# projeson.net
KiCad netlist of a schematic drawn in EAGLE
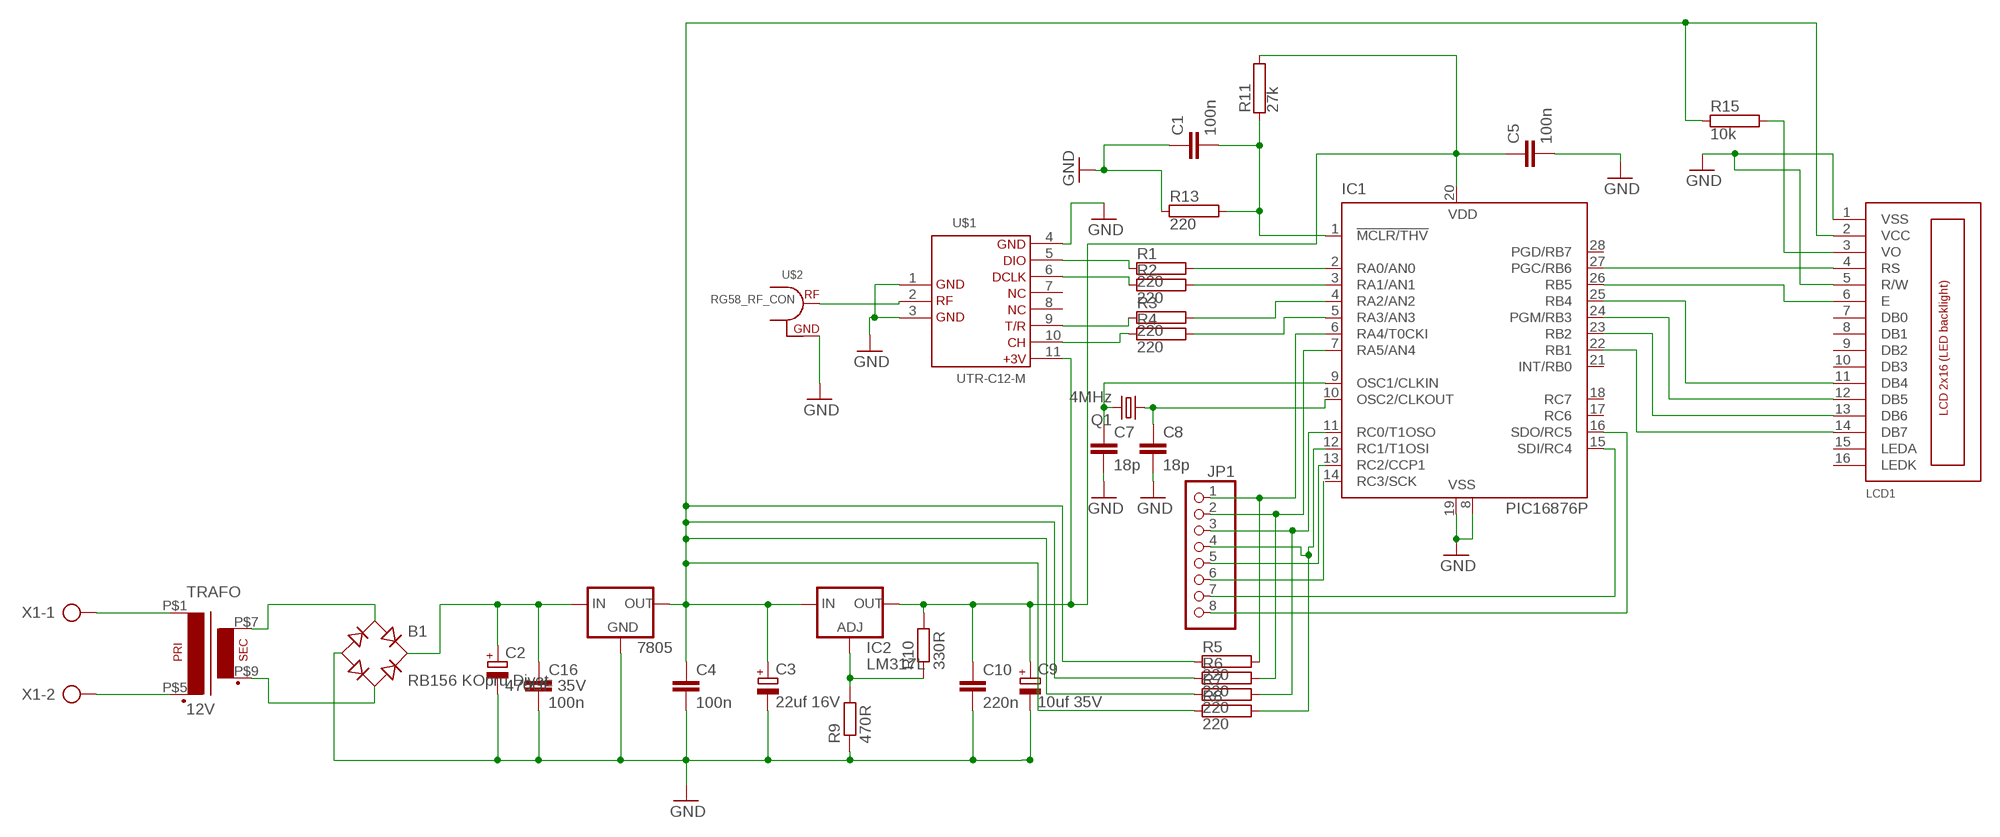
[diagram p0: schematic, sheet 1]

(export (version "E")
  (design (tool "Eeschema 10.0.6"))
  (components
    (comp (ref "7805")
      (value "78XXS")
      (footprint "eagle-import:78XXS")
      (libsource (lib "eagle-import") (part "78XXS"))
    )
    (comp (ref "B1")
      (value "RB156 KOpru Diyot")
      (footprint "eagle-import:RB1A")
      (libsource (lib "eagle-import") (part "RB1A"))
    )
    (comp (ref "C1")
      (value "100n")
      (footprint "eagle-import:C025-030X050")
      (libsource (lib "eagle-import") (part "C-EU025-030X050"))
    )
    (comp (ref "C2")
      (value "470UF 35V")
      (footprint "eagle-import:E3,5-10")
      (libsource (lib "eagle-import") (part "CPOL-EUE3.5-10"))
    )
    (comp (ref "C3")
      (value "22uf 16V")
      (footprint "eagle-import:E2,5-7")
      (libsource (lib "eagle-import") (part "CPOL-EUE2.5-7"))
    )
    (comp (ref "C4")
      (value "100n")
      (footprint "eagle-import:C050-025X075")
      (libsource (lib "eagle-import") (part "C-EU050-025X075"))
    )
    (comp (ref "C5")
      (value "100n")
      (footprint "eagle-import:C025-025X050")
      (libsource (lib "eagle-import") (part "C-EU025-025X050"))
    )
    (comp (ref "C7")
      (value "18p")
      (footprint "eagle-import:C025-025X050")
      (libsource (lib "eagle-import") (part "C-EU025-025X050"))
    )
    (comp (ref "C8")
      (value "18p")
      (footprint "eagle-import:C025-025X050")
      (libsource (lib "eagle-import") (part "C-EU025-025X050"))
    )
    (comp (ref "C9")
      (value "10uf 35V")
      (footprint "eagle-import:E2,5-7")
      (libsource (lib "eagle-import") (part "CPOL-EUE2.5-7"))
    )
    (comp (ref "C10")
      (value "220n")
      (footprint "eagle-import:C050-025X075")
      (libsource (lib "eagle-import") (part "C-EU050-025X075"))
    )
    (comp (ref "C16")
      (value "100n")
      (footprint "eagle-import:C050-025X075")
      (libsource (lib "eagle-import") (part "C-EU050-025X075"))
    )
    (comp (ref "IC1")
      (value "PIC16876P")
      (footprint "eagle-import:DIL28-3")
      (libsource (lib "eagle-import") (part "PIC16876P"))
    )
    (comp (ref "IC2")
      (value "LM317L")
      (footprint "eagle-import:317L")
      (libsource (lib "eagle-import") (part "LM317L"))
    )
    (comp (ref "JP1")
      (value "PINHD-1X8")
      (footprint "eagle-import:1X08")
      (libsource (lib "eagle-import") (part "PINHD-1X8"))
    )
    (comp (ref "LCD1")
      (value "LCD_2X16_SIL")
      (footprint "eagle-import:HY-1602F")
      (libsource (lib "eagle-import") (part "LCD_2X16_SIL"))
    )
    (comp (ref "Q1")
      (value "4MHz")
      (footprint "eagle-import:HC49_S")
      (libsource (lib "eagle-import") (part "CRYTALHC49S"))
    )
    (comp (ref "R1")
      (value "220")
      (footprint "eagle-import:AC04")
      (libsource (lib "eagle-import") (part "RAC04"))
    )
    (comp (ref "R2")
      (value "220")
      (footprint "eagle-import:AC04")
      (libsource (lib "eagle-import") (part "RAC04"))
    )
    (comp (ref "R3")
      (value "220")
      (footprint "eagle-import:AC04")
      (libsource (lib "eagle-import") (part "RAC04"))
    )
    (comp (ref "R4")
      (value "220")
      (footprint "eagle-import:AC04")
      (libsource (lib "eagle-import") (part "RAC04"))
    )
    (comp (ref "R5")
      (value "220")
      (footprint "eagle-import:AC04")
      (libsource (lib "eagle-import") (part "RAC04"))
    )
    (comp (ref "R6")
      (value "220")
      (footprint "eagle-import:AC04")
      (libsource (lib "eagle-import") (part "RAC04"))
    )
    (comp (ref "R7")
      (value "220")
      (footprint "eagle-import:AC04")
      (libsource (lib "eagle-import") (part "RAC04"))
    )
    (comp (ref "R8")
      (value "220")
      (footprint "eagle-import:AC04")
      (libsource (lib "eagle-import") (part "RAC04"))
    )
    (comp (ref "R9")
      (value "470R")
      (footprint "eagle-import:0207_10")
      (libsource (lib "eagle-import") (part "R-EU_0207/10"))
    )
    (comp (ref "R10")
      (value "330R")
      (footprint "eagle-import:0207_10")
      (libsource (lib "eagle-import") (part "R-EU_0207/10"))
    )
    (comp (ref "R11")
      (value "27k")
      (footprint "eagle-import:AC04")
      (libsource (lib "eagle-import") (part "RAC04"))
    )
    (comp (ref "R13")
      (value "220")
      (footprint "eagle-import:AC04")
      (libsource (lib "eagle-import") (part "RAC04"))
    )
    (comp (ref "R15")
      (value "10k")
      (footprint "eagle-import:AC04")
      (libsource (lib "eagle-import") (part "RAC04"))
    )
    (comp (ref "TRAFO")
      (value "12V")
      (footprint "eagle-import:E3031TRF")
      (libsource (lib "eagle-import") (part "TRAFO"))
    )
    (comp (ref "U$1")
      (value "UTR-C12-M")
      (footprint "eagle-import:UTR-C12-M")
      (libsource (lib "eagle-import") (part "UTR-C12-M"))
    )
    (comp (ref "U$2")
      (value "RG58_RF_CON")
      (footprint "eagle-import:RG58_RF_CON")
      (libsource (lib "eagle-import") (part "RG58_RF_CON"))
    )
    (comp (ref "X1")
      (value "AK300/3")
      (footprint "eagle-import:AK300_3")
      (libsource (lib "eagle-import") (part "AK300/3"))
    )
  )
  (nets
    (net (code "1") (name "GND") (class "Default")
      (node (ref "7805") (pin "GND") (pinfunction "GND_GND") (pintype "input"))
      (node (ref "B1") (pin "-") (pinfunction "-_-") (pintype "passive"))
      (node (ref "C1") (pin "1") (pinfunction "1_1") (pintype "passive"))
      (node (ref "C10") (pin "2") (pinfunction "2_2") (pintype "passive"))
      (node (ref "C16") (pin "2") (pinfunction "2_2") (pintype "passive"))
      (node (ref "C2") (pin "-") (pinfunction "-_-") (pintype "passive"))
      (node (ref "C3") (pin "-") (pinfunction "-_-") (pintype "passive"))
      (node (ref "C4") (pin "2") (pinfunction "2_2") (pintype "passive"))
      (node (ref "C5") (pin "2") (pinfunction "2_2") (pintype "passive"))
      (node (ref "C7") (pin "2") (pinfunction "2_2") (pintype "passive"))
      (node (ref "C8") (pin "2") (pinfunction "2_2") (pintype "passive"))
      (node (ref "C9") (pin "-") (pinfunction "-_-") (pintype "passive"))
      (node (ref "IC1") (pin "19") (pinfunction "VSS_19") (pintype "power_in"))
      (node (ref "IC1") (pin "8") (pinfunction "VSS_8") (pintype "power_in"))
      (node (ref "LCD1") (pin "1") (pinfunction "VSS_1") (pintype "power_in"))
      (node (ref "LCD1") (pin "5") (pinfunction "R/W_5") (pintype "input"))
      (node (ref "R13") (pin "1") (pinfunction "1_1") (pintype "passive"))
      (node (ref "R9") (pin "1") (pinfunction "1_1") (pintype "passive"))
      (node (ref "U$1") (pin "1") (pinfunction "1_1") (pintype "bidirectional"))
      (node (ref "U$1") (pin "3") (pinfunction "3_3") (pintype "bidirectional"))
      (node (ref "U$1") (pin "4") (pinfunction "4_4") (pintype "bidirectional"))
      (node (ref "U$2") (pin "GND") (pinfunction "GND_GND") (pintype "bidirectional"))
    )
    (net (code "2") (name "Net-(7805-PadIN)") (class "Default")
      (node (ref "7805") (pin "IN") (pinfunction "IN_IN") (pintype "input"))
      (node (ref "B1") (pin "+") (pinfunction "+_+") (pintype "passive"))
      (node (ref "C16") (pin "1") (pinfunction "1_1") (pintype "passive"))
      (node (ref "C2") (pin "+") (pinfunction "+_+") (pintype "passive"))
    )
    (net (code "3") (name "Net-(IC1-OSC1{slash}CLKIN)") (class "Default")
      (node (ref "C7") (pin "1") (pinfunction "1_1") (pintype "passive"))
      (node (ref "IC1") (pin "9") (pinfunction "OSC1/CLKIN_9") (pintype "input"))
      (node (ref "Q1") (pin "2") (pinfunction "2_2") (pintype "passive"))
    )
    (net (code "4") (name "Net-(IC1-OSC2{slash}CLKOUT)") (class "Default")
      (node (ref "C8") (pin "1") (pinfunction "1_1") (pintype "passive"))
      (node (ref "IC1") (pin "10") (pinfunction "OSC2/CLKOUT_10") (pintype "output"))
      (node (ref "Q1") (pin "1") (pinfunction "1_1") (pintype "passive"))
    )
    (net (code "5") (name "Net-(IC1-PGC{slash}RB6)") (class "Default")
      (node (ref "IC1") (pin "27") (pinfunction "PGC/RB6_27") (pintype "bidirectional"))
      (node (ref "LCD1") (pin "4") (pinfunction "RS_4") (pintype "input"))
    )
    (net (code "6") (name "Net-(IC1-PGM{slash}RB3)") (class "Default")
      (node (ref "IC1") (pin "24") (pinfunction "PGM/RB3_24") (pintype "bidirectional"))
      (node (ref "LCD1") (pin "12") (pinfunction "DB5_12") (pintype "bidirectional"))
    )
    (net (code "7") (name "Net-(IC1-RA0{slash}AN0)") (class "Default")
      (node (ref "IC1") (pin "2") (pinfunction "RA0/AN0_2") (pintype "bidirectional"))
      (node (ref "R1") (pin "2") (pinfunction "2_2") (pintype "passive"))
    )
    (net (code "8") (name "Net-(IC1-RA1{slash}AN1)") (class "Default")
      (node (ref "IC1") (pin "3") (pinfunction "RA1/AN1_3") (pintype "bidirectional"))
      (node (ref "R2") (pin "2") (pinfunction "2_2") (pintype "passive"))
    )
    (net (code "9") (name "Net-(IC1-RA2{slash}AN2)") (class "Default")
      (node (ref "IC1") (pin "4") (pinfunction "RA2/AN2_4") (pintype "bidirectional"))
      (node (ref "R3") (pin "2") (pinfunction "2_2") (pintype "passive"))
    )
    (net (code "10") (name "Net-(IC1-RA3{slash}AN3)") (class "Default")
      (node (ref "IC1") (pin "5") (pinfunction "RA3/AN3_5") (pintype "bidirectional"))
      (node (ref "R4") (pin "2") (pinfunction "2_2") (pintype "passive"))
    )
    (net (code "11") (name "Net-(IC1-RA4{slash}T0CKI)") (class "Default")
      (node (ref "IC1") (pin "6") (pinfunction "RA4/T0CKI_6") (pintype "bidirectional"))
      (node (ref "JP1") (pin "1") (pinfunction "1_1") (pintype "passive"))
      (node (ref "R5") (pin "2") (pinfunction "2_2") (pintype "passive"))
    )
    (net (code "12") (name "Net-(IC1-RA5{slash}AN4)") (class "Default")
      (node (ref "IC1") (pin "7") (pinfunction "RA5/AN4_7") (pintype "bidirectional"))
      (node (ref "JP1") (pin "2") (pinfunction "2_2") (pintype "passive"))
      (node (ref "R6") (pin "2") (pinfunction "2_2") (pintype "passive"))
    )
    (net (code "13") (name "Net-(IC1-RB1)") (class "Default")
      (node (ref "IC1") (pin "22") (pinfunction "RB1_22") (pintype "bidirectional"))
      (node (ref "LCD1") (pin "14") (pinfunction "DB7_14") (pintype "bidirectional"))
    )
    (net (code "14") (name "Net-(IC1-RB2)") (class "Default")
      (node (ref "IC1") (pin "23") (pinfunction "RB2_23") (pintype "bidirectional"))
      (node (ref "LCD1") (pin "13") (pinfunction "DB6_13") (pintype "bidirectional"))
    )
    (net (code "15") (name "Net-(IC1-RB4)") (class "Default")
      (node (ref "IC1") (pin "25") (pinfunction "RB4_25") (pintype "bidirectional"))
      (node (ref "LCD1") (pin "11") (pinfunction "DB4_11") (pintype "bidirectional"))
    )
    (net (code "16") (name "Net-(IC1-RB5)") (class "Default")
      (node (ref "IC1") (pin "26") (pinfunction "RB5_26") (pintype "bidirectional"))
      (node (ref "LCD1") (pin "6") (pinfunction "E_6") (pintype "input"))
    )
    (net (code "17") (name "Net-(IC1-RC0{slash}T1OSO)") (class "Default")
      (node (ref "IC1") (pin "11") (pinfunction "RC0/T1OSO_11") (pintype "bidirectional"))
      (node (ref "JP1") (pin "3") (pinfunction "3_3") (pintype "passive"))
      (node (ref "R7") (pin "2") (pinfunction "2_2") (pintype "passive"))
    )
    (net (code "18") (name "Net-(IC1-RC1{slash}T1OSI)") (class "Default")
      (node (ref "IC1") (pin "12") (pinfunction "RC1/T1OSI_12") (pintype "bidirectional"))
      (node (ref "JP1") (pin "4") (pinfunction "4_4") (pintype "passive"))
      (node (ref "R8") (pin "2") (pinfunction "2_2") (pintype "passive"))
    )
    (net (code "19") (name "Net-(IC1-RC2{slash}CCP1)") (class "Default")
      (node (ref "IC1") (pin "13") (pinfunction "RC2/CCP1_13") (pintype "bidirectional"))
      (node (ref "JP1") (pin "5") (pinfunction "5_5") (pintype "passive"))
    )
    (net (code "20") (name "Net-(IC1-SDI{slash}RC4)") (class "Default")
      (node (ref "IC1") (pin "15") (pinfunction "SDI/RC4_15") (pintype "bidirectional"))
      (node (ref "JP1") (pin "7") (pinfunction "7_7") (pintype "passive"))
    )
    (net (code "21") (name "Net-(IC1-SDO{slash}RC5)") (class "Default")
      (node (ref "IC1") (pin "16") (pinfunction "SDO/RC5_16") (pintype "bidirectional"))
      (node (ref "JP1") (pin "8") (pinfunction "8_8") (pintype "passive"))
    )
    (net (code "22") (name "Net-(IC1-VDD)") (class "Default")
      (node (ref "C10") (pin "1") (pinfunction "1_1") (pintype "passive"))
      (node (ref "C5") (pin "1") (pinfunction "1_1") (pintype "passive"))
      (node (ref "C9") (pin "+") (pinfunction "+_+") (pintype "passive"))
      (node (ref "IC1") (pin "20") (pinfunction "VDD_20") (pintype "power_in"))
      (node (ref "IC2") (pin "2") (pinfunction "OUT_2") (pintype "passive"))
      (node (ref "R10") (pin "2") (pinfunction "2_2") (pintype "passive"))
      (node (ref "R11") (pin "2") (pinfunction "2_2") (pintype "passive"))
      (node (ref "U$1") (pin "11") (pinfunction "11_11") (pintype "bidirectional"))
    )
    (net (code "23") (name "Net-(IC1-~{MCLR{slash}THV})") (class "Default")
      (node (ref "C1") (pin "2") (pinfunction "2_2") (pintype "passive"))
      (node (ref "IC1") (pin "1") (pinfunction "~{MCLR/THV}_1") (pintype "input"))
      (node (ref "R11") (pin "1") (pinfunction "1_1") (pintype "passive"))
      (node (ref "R13") (pin "2") (pinfunction "2_2") (pintype "passive"))
    )
    (net (code "24") (name "Net-(IC2-ADJ)") (class "Default")
      (node (ref "IC2") (pin "1") (pinfunction "ADJ_1") (pintype "input"))
      (node (ref "R10") (pin "1") (pinfunction "1_1") (pintype "passive"))
      (node (ref "R9") (pin "2") (pinfunction "2_2") (pintype "passive"))
    )
    (net (code "25") (name "Net-(IC2-IN)") (class "Default")
      (node (ref "7805") (pin "OUT") (pinfunction "OUT_OUT") (pintype "passive"))
      (node (ref "C3") (pin "+") (pinfunction "+_+") (pintype "passive"))
      (node (ref "C4") (pin "1") (pinfunction "1_1") (pintype "passive"))
      (node (ref "IC2") (pin "3") (pinfunction "IN_3") (pintype "input"))
      (node (ref "LCD1") (pin "2") (pinfunction "VCC_2") (pintype "power_in"))
      (node (ref "R15") (pin "1") (pinfunction "1_1") (pintype "passive"))
      (node (ref "R5") (pin "1") (pinfunction "1_1") (pintype "passive"))
      (node (ref "R6") (pin "1") (pinfunction "1_1") (pintype "passive"))
      (node (ref "R7") (pin "1") (pinfunction "1_1") (pintype "passive"))
      (node (ref "R8") (pin "1") (pinfunction "1_1") (pintype "passive"))
    )
    (net (code "26") (name "Net-(LCD1-VO)") (class "Default")
      (node (ref "LCD1") (pin "3") (pinfunction "VO_3") (pintype "input"))
      (node (ref "R15") (pin "2") (pinfunction "2_2") (pintype "passive"))
    )
    (net (code "27") (name "Net-(R1-Pad1)") (class "Default")
      (node (ref "R1") (pin "1") (pinfunction "1_1") (pintype "passive"))
      (node (ref "U$1") (pin "5") (pinfunction "5_5") (pintype "bidirectional"))
    )
    (net (code "28") (name "Net-(R2-Pad1)") (class "Default")
      (node (ref "R2") (pin "1") (pinfunction "1_1") (pintype "passive"))
      (node (ref "U$1") (pin "6") (pinfunction "6_6") (pintype "bidirectional"))
    )
    (net (code "29") (name "Net-(R3-Pad1)") (class "Default")
      (node (ref "R3") (pin "1") (pinfunction "1_1") (pintype "passive"))
      (node (ref "U$1") (pin "9") (pinfunction "9_9") (pintype "bidirectional"))
    )
    (net (code "30") (name "Net-(R4-Pad1)") (class "Default")
      (node (ref "R4") (pin "1") (pinfunction "1_1") (pintype "passive"))
      (node (ref "U$1") (pin "10") (pinfunction "10_10") (pintype "bidirectional"))
    )
    (net (code "31") (name "Net-(TRAFO-1)") (class "Default")
      (node (ref "TRAFO") (pin "P$1") (pinfunction "1_P$1") (pintype "passive"))
      (node (ref "X1") (pin "1") (pinfunction "KL_1") (pintype "passive"))
    )
    (net (code "32") (name "Net-(TRAFO-5)") (class "Default")
      (node (ref "TRAFO") (pin "P$5") (pinfunction "5_P$5") (pintype "passive"))
      (node (ref "X1") (pin "2") (pinfunction "KL_2") (pintype "passive"))
    )
    (net (code "33") (name "Net-(TRAFO-7)") (class "Default")
      (node (ref "B1") (pin "AC1") (pinfunction "AC1_AC1") (pintype "passive"))
      (node (ref "TRAFO") (pin "P$7") (pinfunction "7_P$7") (pintype "passive"))
    )
    (net (code "34") (name "Net-(TRAFO-9)") (class "Default")
      (node (ref "B1") (pin "AC2") (pinfunction "AC2_AC2") (pintype "passive"))
      (node (ref "TRAFO") (pin "P$9") (pinfunction "9_P$9") (pintype "passive"))
    )
    (net (code "35") (name "Net-(U$1-Pad2)") (class "Default")
      (node (ref "U$1") (pin "2") (pinfunction "2_2") (pintype "bidirectional"))
      (node (ref "U$2") (pin "RF") (pinfunction "RF_RF") (pintype "bidirectional"))
    )
    (net (code "36") (name "unconnected-(IC1-INT{slash}RB0-Pad21)") (class "Default")
      (node (ref "IC1") (pin "21") (pinfunction "INT/RB0_21") (pintype "bidirectional"))
    )
    (net (code "37") (name "unconnected-(IC1-PGD{slash}RB7-Pad28)") (class "Default")
      (node (ref "IC1") (pin "28") (pinfunction "PGD/RB7_28") (pintype "bidirectional"))
    )
    (net (code "38") (name "unconnected-(IC1-RC3{slash}SCK-Pad14)") (class "Default")
      (node (ref "IC1") (pin "14") (pinfunction "RC3/SCK_14") (pintype "bidirectional"))
    )
    (net (code "39") (name "unconnected-(IC1-RC6-Pad17)") (class "Default")
      (node (ref "IC1") (pin "17") (pinfunction "RC6_17") (pintype "bidirectional"))
    )
    (net (code "40") (name "unconnected-(IC1-RC7-Pad18)") (class "Default")
      (node (ref "IC1") (pin "18") (pinfunction "RC7_18") (pintype "bidirectional"))
    )
    (net (code "41") (name "unconnected-(JP1-Pad6)") (class "Default")
      (node (ref "JP1") (pin "6") (pinfunction "6_6") (pintype "passive"))
    )
    (net (code "42") (name "unconnected-(LCD1-DB0-Pad7)") (class "Default")
      (node (ref "LCD1") (pin "7") (pinfunction "DB0_7") (pintype "bidirectional"))
    )
    (net (code "43") (name "unconnected-(LCD1-DB1-Pad8)") (class "Default")
      (node (ref "LCD1") (pin "8") (pinfunction "DB1_8") (pintype "bidirectional"))
    )
    (net (code "44") (name "unconnected-(LCD1-DB2-Pad9)") (class "Default")
      (node (ref "LCD1") (pin "9") (pinfunction "DB2_9") (pintype "bidirectional"))
    )
    (net (code "45") (name "unconnected-(LCD1-DB3-Pad10)") (class "Default")
      (node (ref "LCD1") (pin "10") (pinfunction "DB3_10") (pintype "bidirectional"))
    )
    (net (code "46") (name "unconnected-(LCD1-LEDA-Pad15)") (class "Default")
      (node (ref "LCD1") (pin "15") (pinfunction "LEDA_15") (pintype "passive"))
    )
    (net (code "47") (name "unconnected-(LCD1-LEDK-Pad16)") (class "Default")
      (node (ref "LCD1") (pin "16") (pinfunction "LEDK_16") (pintype "passive"))
    )
    (net (code "48") (name "unconnected-(U$1-Pad7)") (class "Default")
      (node (ref "U$1") (pin "7") (pinfunction "7_7") (pintype "bidirectional"))
    )
    (net (code "49") (name "unconnected-(U$1-Pad8)") (class "Default")
      (node (ref "U$1") (pin "8") (pinfunction "8_8") (pintype "bidirectional"))
    )
  )
)
